# Powersupply.net
KiCad netlist of a schematic drawn in EAGLE
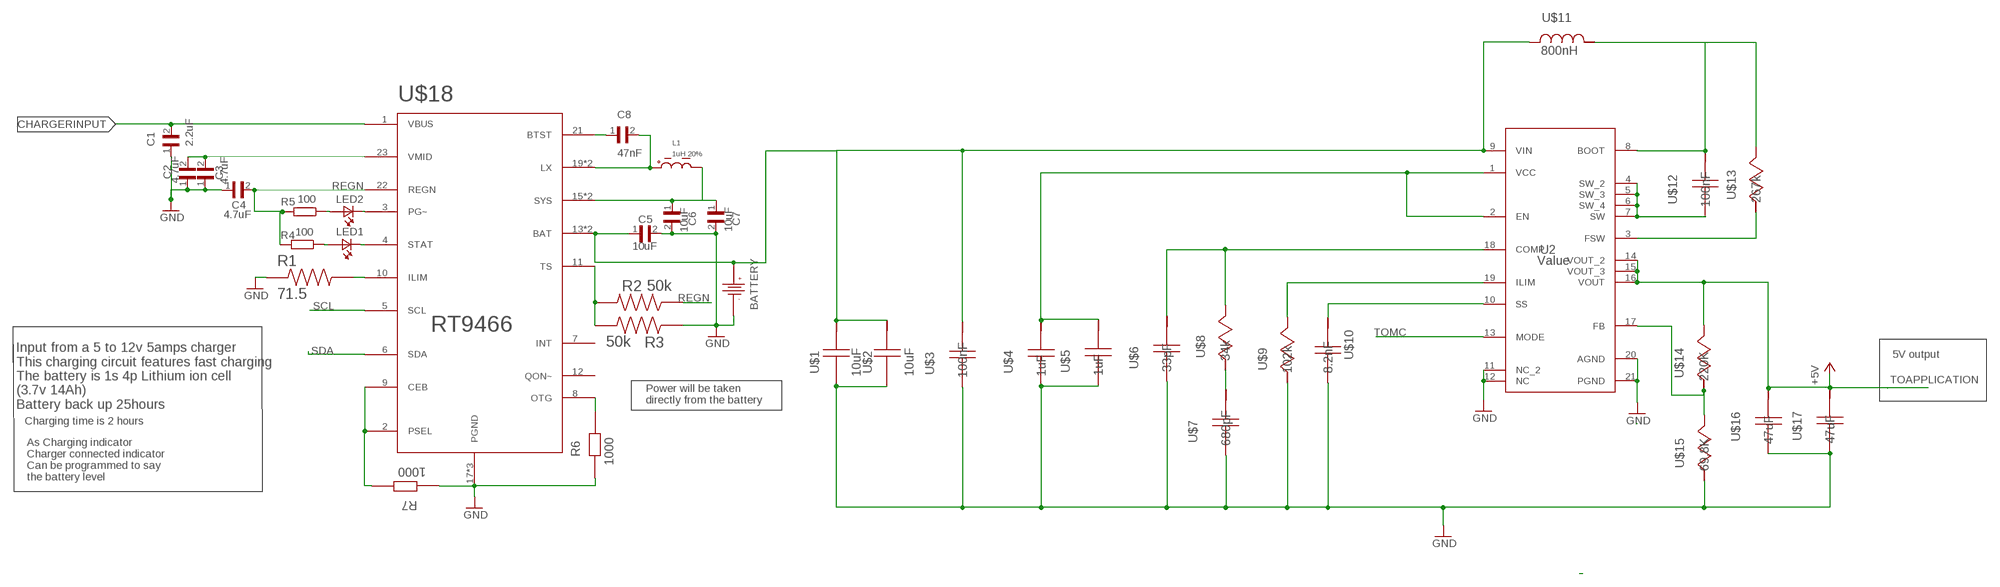
[diagram p0: schematic, sheet 1]

(export (version "E")
  (design (tool "Eeschema 10.0.6"))
  (components
    (comp (ref "BATT1")
      (value "BATPADS")
      (footprint "eagle-import:PADSBATT")
      (libsource (lib "eagle-import") (part "BATPADS"))
    )
    (comp (ref "C1")
      (value "2.2uF")
      (footprint "eagle-import:CAPC1005X70N")
      (fields
        (field (name "DIGI-KEY_PART_NUMBER") "490-12703-1-ND")
        (field (name "MF") "Murata")
        (field (name "MP") "GRM155R61E225KE11D")
      )
      (libsource (lib "eagle-import") (part "GRM155R61E225KE11D"))
    )
    (comp (ref "C2")
      (value "4.7uF")
      (footprint "eagle-import:CAPC1608X95N")
      (fields
        (field (name "DIGI-KEY_PART_NUMBER") "490-7203-1-ND")
        (field (name "MF") "Murata")
        (field (name "MP") "GRM188R61E475KE11D")
      )
      (libsource (lib "eagle-import") (part "GRM188R61E475KE11D"))
    )
    (comp (ref "C3")
      (value "4.7uF")
      (footprint "eagle-import:CAPC1608X95N")
      (fields
        (field (name "DIGI-KEY_PART_NUMBER") "490-7203-1-ND")
        (field (name "MF") "Murata")
        (field (name "MP") "GRM188R61E475KE11D")
      )
      (libsource (lib "eagle-import") (part "GRM188R61E475KE11D"))
    )
    (comp (ref "C4")
      (value "4.7uF")
      (footprint "eagle-import:CAPC1608X95N")
      (fields
        (field (name "DIGI-KEY_PART_NUMBER") "490-7203-1-ND")
        (field (name "MF") "Murata")
        (field (name "MP") "GRM188R61E475KE11D")
      )
      (libsource (lib "eagle-import") (part "GRM188R61E475KE11D"))
    )
    (comp (ref "C5")
      (value "10uF")
      (footprint "eagle-import:CAPC1608X50N")
      (fields
        (field (name "DIGI-KEY_PART_NUMBER") "490-16349-1-ND")
        (field (name "MF") "Murata")
        (field (name "MP") "GRM185R60J106ME15J")
      )
      (libsource (lib "eagle-import") (part "GRM185R60J106ME15J"))
    )
    (comp (ref "C6")
      (value "10uF")
      (footprint "eagle-import:CAPC1608X50N")
      (fields
        (field (name "DIGI-KEY_PART_NUMBER") "490-16349-1-ND")
        (field (name "MF") "Murata")
        (field (name "MP") "GRM185R60J106ME15J")
      )
      (libsource (lib "eagle-import") (part "GRM185R60J106ME15J"))
    )
    (comp (ref "C7")
      (value "10uF")
      (footprint "eagle-import:CAPC1608X50N")
      (fields
        (field (name "DIGI-KEY_PART_NUMBER") "490-16349-1-ND")
        (field (name "MF") "Murata")
        (field (name "MP") "GRM185R60J106ME15J")
      )
      (libsource (lib "eagle-import") (part "GRM185R60J106ME15J"))
    )
    (comp (ref "C8")
      (value "47nF")
      (footprint "eagle-import:CAPC0603X33N")
      (fields
        (field (name "DIGI-KEY_PART_NUMBER") "490-7227-1-ND")
        (field (name "MF") "Murata")
        (field (name "MP") "GRM033R61C473KE84D")
      )
      (libsource (lib "eagle-import") (part "GRM033R61C473KE84D"))
    )
    (comp (ref "L1")
      (value "1uH 20%")
      (footprint "eagle-import:4020")
      (fields (field (name "MANUFACTURER") "Würth Elektronik") (field (name "PARTNO") "74438356010"))
      (libsource (lib "eagle-import") (part "74438356010"))
    )
    (comp (ref "LED1")
      (value "LTST-C191KGKT")
      (footprint "eagle-import:0603")
      (fields (field (name "DIGI-KEY_PART_NUMBER") "160-1446-1-ND") (field (name "MF") "Lite-On Inc."))
      (libsource (lib "eagle-import") (part "LTST-C191KGKT"))
    )
    (comp (ref "LED2")
      (value "LTST-C191KGKT")
      (footprint "eagle-import:0603")
      (fields (field (name "DIGI-KEY_PART_NUMBER") "160-1446-1-ND") (field (name "MF") "Lite-On Inc."))
      (libsource (lib "eagle-import") (part "LTST-C191KGKT"))
    )
    (comp (ref "R1")
      (value "71.5")
      (footprint "eagle-import:RESC1005X40N")
      (fields
        (field (name "DIGI-KEY_PART_NUMBER") "YAG3223CT-ND")
        (field (name "MF") "Yageo")
        (field (name "MP") "RC0402FR-0771R5L")
      )
      (libsource (lib "eagle-import") (part "RC0402FR-0771R5L"))
    )
    (comp (ref "R2")
      (value "50k")
      (footprint "eagle-import:RESC1608X55N")
      (fields
        (field (name "DIGI-KEY_PART_NUMBER") "P49.9KDBCT-ND")
        (field (name "MF") "Panasonic")
        (field (name "MP") "ERA-3AEB4992V")
      )
      (libsource (lib "eagle-import") (part "ERA-3AEB4992V"))
    )
    (comp (ref "R3")
      (value "50k")
      (footprint "eagle-import:RESC1608X55N")
      (fields
        (field (name "DIGI-KEY_PART_NUMBER") "P49.9KDBCT-ND")
        (field (name "MF") "Panasonic")
        (field (name "MP") "ERA-3AEB4992V")
      )
      (libsource (lib "eagle-import") (part "ERA-3AEB4992V"))
    )
    (comp (ref "R4")
      (value "RX0402_100")
      (footprint "eagle-import:RC0402_100")
      (libsource (lib "eagle-import") (part "RX0402_100"))
    )
    (comp (ref "R5")
      (value "RX0402_100")
      (footprint "eagle-import:RC0402_100")
      (libsource (lib "eagle-import") (part "RX0402_100"))
    )
    (comp (ref "R6")
      (value "1000")
      (footprint "eagle-import:RESC1005X40N")
      (fields
        (field (name "DIGI-KEY_PART_NUMBER") "P1.0KJCT-ND")
        (field (name "MF") "Panasonic Electronic")
        (field (name "MP") "ERJ-2GEJ102X")
      )
      (libsource (lib "eagle-import") (part "ERJ-2GEJ102X"))
    )
    (comp (ref "R7")
      (value "1000")
      (footprint "eagle-import:RESC1005X40N")
      (fields
        (field (name "DIGI-KEY_PART_NUMBER") "P1.0KJCT-ND")
        (field (name "MF") "Panasonic Electronic")
        (field (name "MP") "ERJ-2GEJ102X")
      )
      (libsource (lib "eagle-import") (part "ERJ-2GEJ102X"))
    )
    (comp (ref "U$1")
      (value "10uF")
      (footprint "eagle-import:1206_190")
      (fields (field (name "MANUFACTURER_PART_NUMBER") "CC1206ZKY5V7BB106"))
      (libsource (lib "eagle-import") (part "CC1206ZKY5V7BB106"))
    )
    (comp (ref "U$2")
      (value "10uF")
      (footprint "eagle-import:1206_190")
      (fields (field (name "MANUFACTURER_PART_NUMBER") "CC1206ZKY5V7BB106"))
      (libsource (lib "eagle-import") (part "CC1206ZKY5V7BB106"))
    )
    (comp (ref "U$3")
      (value "100nF")
      (footprint "eagle-import:0402")
      (fields (field (name "MANUFACTURER_PART_NUMBER") "CC0402KRX7R6BB104"))
      (libsource (lib "eagle-import") (part "CC0402KRX7R6BB104"))
    )
    (comp (ref "U$4")
      (value "1uF")
      (footprint "eagle-import:0603")
      (fields (field (name "MANUFACTURER_PART_NUMBER") "EMK107B7105KAT") (field (name "SPICEPREFIX") "B"))
      (libsource (lib "eagle-import") (part "EMK107B7105KA-T"))
    )
    (comp (ref "U$5")
      (value "1uF")
      (footprint "eagle-import:0603")
      (fields (field (name "MANUFACTURER_PART_NUMBER") "EMK107B7105KAT"))
      (libsource (lib "eagle-import") (part "EMK107B7105KA-T"))
    )
    (comp (ref "U$6")
      (value "33pF")
      (footprint "eagle-import:0402")
      (fields (field (name "MANUFACTURER_PART_NUMBER") "885012005043"))
      (libsource (lib "eagle-import") (part "885012005043"))
    )
    (comp (ref "U$7")
      (value "680pF")
      (footprint "eagle-import:0603")
      (fields (field (name "MANUFACTURER_PART_NUMBER") "CL10C681JA8NNNC"))
      (libsource (lib "eagle-import") (part "CL10C681JA8NNNC"))
    )
    (comp (ref "U$8")
      (value "34k")
      (footprint "eagle-import:0402")
      (fields
        (field (name "MANUFACTURER_PART_NUMBER") "CRCW040234K0FKED")
        (field (name "POWER") "0.063")
        (field (name "TOLERANCE") "1.0")
      )
      (libsource (lib "eagle-import") (part "CRCW040234K0FKED"))
    )
    (comp (ref "U$9")
      (value "102k")
      (footprint "eagle-import:0402")
      (fields
        (field (name "MANUFACTURER_PART_NUMBER") "CRCW0402102KFKED")
        (field (name "POWER") "0.063")
        (field (name "TOLERANCE") "1.0")
      )
      (libsource (lib "eagle-import") (part "CRCW0402102KFKED"))
    )
    (comp (ref "U$10")
      (value "8.2nF")
      (footprint "eagle-import:0402")
      (fields (field (name "MANUFACTURER_PART_NUMBER") "CC0402KRX7R7BB822"))
      (libsource (lib "eagle-import") (part "CC0402KRX7R7BB822"))
    )
    (comp (ref "U$11")
      (value "800nH")
      (footprint "eagle-import:XAL5020")
      (fields
        (field (name "MANUFACTURER") "CoilCraft")
        (field (name "MANUFACTURER_PART_NUMBER") "XAL5020801MEB")
      )
      (libsource (lib "eagle-import") (part "XAL5020-801MEB"))
    )
    (comp (ref "U$12")
      (value "100nF")
      (footprint "eagle-import:0402")
      (fields (field (name "MANUFACTURER_PART_NUMBER") "/CC0402KRX5R7BB104"))
      (libsource (lib "eagle-import") (part "CC0402KRX5R7BB104"))
    )
    (comp (ref "U$13")
      (value "267k")
      (footprint "eagle-import:0402")
      (fields
        (field (name "MANUFACTURER_PART_NUMBER") "CRCW0402267KFKED")
        (field (name "POWER") "0.063")
        (field (name "TOLERANCE") "1.0")
      )
      (libsource (lib "eagle-import") (part "CRCW0402267KFKED"))
    )
    (comp (ref "U$14")
      (value "220K")
      (footprint "eagle-import:0603")
      (fields
        (field (name "MANUFACTURER_PART_NUMBER") "RC0603FR07220KL")
        (field (name "POWER") "0.1")
        (field (name "TOLERANCE") "1.0")
      )
      (libsource (lib "eagle-import") (part "RC0603FR-07220KL"))
    )
    (comp (ref "U$15")
      (value "69.8K")
      (footprint "eagle-import:0402")
      (fields
        (field (name "MANUFACTURER_PART_NUMBER") "CRCW040269K8FKED")
        (field (name "POWER") "0.063")
        (field (name "TOLERANCE") "1.0")
      )
      (libsource (lib "eagle-import") (part "CRCW040269K8FKED"))
    )
    (comp (ref "U$16")
      (value "47uF")
      (footprint "eagle-import:2220_250")
      (fields (field (name "MANUFACTURER_PART_NUMBER") "C5750X5R1C476M230KA"))
      (libsource (lib "eagle-import") (part "C5750X5R1C476M230KA"))
    )
    (comp (ref "U$17")
      (value "47uF")
      (footprint "eagle-import:2220_250")
      (fields (field (name "MANUFACTURER_PART_NUMBER") "C5750X5R1C476M230KA"))
      (libsource (lib "eagle-import") (part "C5750X5R1C476M230KA"))
    )
    (comp (ref "U$18")
      (value "RT9466")
      (footprint "eagle-import:V_W_U_XQFN4_4-24")
      (fields (field (name "MANUFACTURER") "Richtek USA Inc."))
      (libsource (lib "eagle-import") (part "RT9466"))
    )
    (comp (ref "U2")
      (value "Value")
      (footprint "eagle-import:RHL0020A")
      (fields
        (field (name "ALTERNATEPARTNUMBER") "TPS61088RHLT")
        (field (name "MANUFACTURER") "Texas Instruments")
        (field (name "MANUFACTURER_PART_NUMBER") "TPS61088RHLR")
      )
      (libsource (lib "eagle-import") (part "TPS61088RHLR"))
    )
  )
  (nets
    (net (code "1") (name "+5V") (class "Default")
      (node (ref "U$14") (pin "1") (pinfunction "1_1") (pintype "passive"))
      (node (ref "U$16") (pin "1") (pinfunction "1_1") (pintype "passive"))
      (node (ref "U$17") (pin "1") (pinfunction "1_1") (pintype "passive"))
      (node (ref "U2") (pin "14") (pinfunction "VOUT_2_14") (pintype "power_in"))
      (node (ref "U2") (pin "15") (pinfunction "VOUT_3_15") (pintype "power_in"))
      (node (ref "U2") (pin "16") (pinfunction "VOUT_16") (pintype "power_in"))
    )
    (net (code "2") (name "/REGN") (class "Default")
      (node (ref "C4") (pin "2") (pinfunction "2_2") (pintype "passive"))
      (node (ref "R2") (pin "1") (pinfunction "1_1") (pintype "passive"))
      (node (ref "R4") (pin "P$2") (pinfunction "2_P$2") (pintype "passive"))
      (node (ref "R5") (pin "P$2") (pinfunction "2_P$2") (pintype "passive"))
      (node (ref "U$18") (pin "22") (pinfunction "REGN_22") (pintype "bidirectional"))
    )
    (net (code "3") (name "/SCL") (class "Default")
      (node (ref "U$18") (pin "5") (pinfunction "SCL_5") (pintype "bidirectional"))
    )
    (net (code "4") (name "/SDA") (class "Default")
      (node (ref "U$18") (pin "6") (pinfunction "SDA_6") (pintype "bidirectional"))
    )
    (net (code "5") (name "/TOMC") (class "Default")
      (node (ref "U2") (pin "13") (pinfunction "MODE_13") (pintype "input"))
    )
    (net (code "6") (name "CHARGERINPUT") (class "Default")
      (node (ref "C1") (pin "2") (pinfunction "2_2") (pintype "passive"))
      (node (ref "U$18") (pin "1") (pinfunction "VBUS_1") (pintype "bidirectional"))
    )
    (net (code "7") (name "GND") (class "Default")
      (node (ref "BATT1") (pin "2") (pinfunction "P$2_2") (pintype "bidirectional"))
      (node (ref "C1") (pin "1") (pinfunction "1_1") (pintype "passive"))
      (node (ref "C2") (pin "1") (pinfunction "1_1") (pintype "passive"))
      (node (ref "C3") (pin "1") (pinfunction "1_1") (pintype "passive"))
      (node (ref "C4") (pin "1") (pinfunction "1_1") (pintype "passive"))
      (node (ref "C5") (pin "2") (pinfunction "2_2") (pintype "passive"))
      (node (ref "C6") (pin "2") (pinfunction "2_2") (pintype "passive"))
      (node (ref "C7") (pin "2") (pinfunction "2_2") (pintype "passive"))
      (node (ref "R1") (pin "1") (pinfunction "1_1") (pintype "passive"))
      (node (ref "R3") (pin "2") (pinfunction "2_2") (pintype "passive"))
      (node (ref "R6") (pin "1") (pinfunction "1_1") (pintype "bidirectional"))
      (node (ref "R7") (pin "1") (pinfunction "1_1") (pintype "bidirectional"))
      (node (ref "U$1") (pin "2") (pinfunction "2_2") (pintype "passive"))
      (node (ref "U$10") (pin "2") (pinfunction "2_2") (pintype "passive"))
      (node (ref "U$15") (pin "2") (pinfunction "2_2") (pintype "passive"))
      (node (ref "U$16") (pin "2") (pinfunction "2_2") (pintype "passive"))
      (node (ref "U$17") (pin "2") (pinfunction "2_2") (pintype "passive"))
      (node (ref "U$18") (pin "17") (pinfunction "PGND_17") (pintype "bidirectional"))
      (node (ref "U$18") (pin "18") (pinfunction "PGND_18") (pintype "bidirectional"))
      (node (ref "U$18") (pin "25") (pinfunction "PGND_25") (pintype "bidirectional"))
      (node (ref "U$2") (pin "2") (pinfunction "2_2") (pintype "passive"))
      (node (ref "U$3") (pin "2") (pinfunction "2_2") (pintype "passive"))
      (node (ref "U$4") (pin "2") (pinfunction "2_2") (pintype "passive"))
      (node (ref "U$5") (pin "2") (pinfunction "2_2") (pintype "passive"))
      (node (ref "U$6") (pin "2") (pinfunction "2_2") (pintype "passive"))
      (node (ref "U$7") (pin "2") (pinfunction "2_2") (pintype "passive"))
      (node (ref "U$9") (pin "2") (pinfunction "2_2") (pintype "passive"))
      (node (ref "U2") (pin "11") (pinfunction "NC_2_11") (pintype "passive"))
      (node (ref "U2") (pin "12") (pinfunction "NC_12") (pintype "passive"))
      (node (ref "U2") (pin "20") (pinfunction "AGND_20") (pintype "power_in"))
      (node (ref "U2") (pin "21") (pinfunction "PGND_21") (pintype "power_in"))
    )
    (net (code "8") (name "Net-(BATT1-P$1)") (class "Default")
      (node (ref "BATT1") (pin "1") (pinfunction "P$1_1") (pintype "bidirectional"))
      (node (ref "C5") (pin "1") (pinfunction "1_1") (pintype "passive"))
      (node (ref "U$1") (pin "1") (pinfunction "1_1") (pintype "passive"))
      (node (ref "U$11") (pin "1") (pinfunction "1_1") (pintype "passive"))
      (node (ref "U$18") (pin "13") (pinfunction "BAT_13") (pintype "bidirectional"))
      (node (ref "U$18") (pin "14") (pinfunction "BAT_14") (pintype "bidirectional"))
      (node (ref "U$2") (pin "1") (pinfunction "1_1") (pintype "passive"))
      (node (ref "U$3") (pin "1") (pinfunction "1_1") (pintype "passive"))
      (node (ref "U2") (pin "9") (pinfunction "VIN_9") (pintype "power_in"))
    )
    (net (code "9") (name "Net-(C6-Pad1)") (class "Default")
      (node (ref "C6") (pin "1") (pinfunction "1_1") (pintype "passive"))
      (node (ref "C7") (pin "1") (pinfunction "1_1") (pintype "passive"))
      (node (ref "L1") (pin "P$2") (pinfunction "P$2_P$2") (pintype "bidirectional"))
      (node (ref "U$18") (pin "15") (pinfunction "SYS_15") (pintype "bidirectional"))
      (node (ref "U$18") (pin "16") (pinfunction "SYS_16") (pintype "bidirectional"))
    )
    (net (code "10") (name "Net-(C8-Pad2)") (class "Default")
      (node (ref "C8") (pin "2") (pinfunction "2_2") (pintype "passive"))
      (node (ref "L1") (pin "P$1") (pinfunction "P$1_P$1") (pintype "bidirectional"))
      (node (ref "U$18") (pin "19") (pinfunction "LX_19") (pintype "bidirectional"))
      (node (ref "U$18") (pin "20") (pinfunction "LX_20") (pintype "bidirectional"))
    )
    (net (code "11") (name "Net-(LED1-A2)") (class "Default")
      (node (ref "LED1") (pin "2") (pinfunction "A2_2") (pintype "passive"))
      (node (ref "R4") (pin "P$1") (pinfunction "1_P$1") (pintype "passive"))
    )
    (net (code "12") (name "Net-(LED1-K2)") (class "Default")
      (node (ref "LED1") (pin "1") (pinfunction "K2_1") (pintype "passive"))
      (node (ref "U$18") (pin "4") (pinfunction "STAT_4") (pintype "bidirectional"))
    )
    (net (code "13") (name "Net-(LED2-A2)") (class "Default")
      (node (ref "LED2") (pin "2") (pinfunction "A2_2") (pintype "passive"))
      (node (ref "R5") (pin "P$1") (pinfunction "1_P$1") (pintype "passive"))
    )
    (net (code "14") (name "Net-(LED2-K2)") (class "Default")
      (node (ref "LED2") (pin "1") (pinfunction "K2_1") (pintype "passive"))
      (node (ref "U$18") (pin "3") (pinfunction "PG~{}_3") (pintype "bidirectional"))
    )
    (net (code "15") (name "Net-(U$7-Pad1)") (class "Default")
      (node (ref "U$7") (pin "1") (pinfunction "1_1") (pintype "passive"))
      (node (ref "U$8") (pin "2") (pinfunction "2_2") (pintype "passive"))
    )
    (net (code "16") (name "Net-(U$18-BTST)") (class "Default")
      (node (ref "C8") (pin "1") (pinfunction "1_1") (pintype "passive"))
      (node (ref "U$18") (pin "21") (pinfunction "BTST_21") (pintype "bidirectional"))
    )
    (net (code "17") (name "Net-(U$18-CEB)") (class "Default")
      (node (ref "R7") (pin "2") (pinfunction "2_2") (pintype "bidirectional"))
      (node (ref "U$18") (pin "2") (pinfunction "PSEL_2") (pintype "bidirectional"))
      (node (ref "U$18") (pin "9") (pinfunction "CEB_9") (pintype "bidirectional"))
    )
    (net (code "18") (name "Net-(U$18-ILIM)") (class "Default")
      (node (ref "R1") (pin "2") (pinfunction "2_2") (pintype "passive"))
      (node (ref "U$18") (pin "10") (pinfunction "ILIM_10") (pintype "bidirectional"))
    )
    (net (code "19") (name "Net-(U$18-OTG)") (class "Default")
      (node (ref "R6") (pin "2") (pinfunction "2_2") (pintype "bidirectional"))
      (node (ref "U$18") (pin "8") (pinfunction "OTG_8") (pintype "bidirectional"))
    )
    (net (code "20") (name "Net-(U$18-TS)") (class "Default")
      (node (ref "R2") (pin "2") (pinfunction "2_2") (pintype "passive"))
      (node (ref "R3") (pin "1") (pinfunction "1_1") (pintype "passive"))
      (node (ref "U$18") (pin "11") (pinfunction "TS_11") (pintype "bidirectional"))
    )
    (net (code "21") (name "Net-(U$18-VMID)") (class "Default")
      (node (ref "C2") (pin "2") (pinfunction "2_2") (pintype "passive"))
      (node (ref "C3") (pin "2") (pinfunction "2_2") (pintype "passive"))
      (node (ref "U$18") (pin "23") (pinfunction "VMID_23") (pintype "bidirectional"))
    )
    (net (code "22") (name "Net-(U2-BOOT)") (class "Default")
      (node (ref "U$11") (pin "2") (pinfunction "2_2") (pintype "passive"))
      (node (ref "U$12") (pin "1") (pinfunction "1_1") (pintype "passive"))
      (node (ref "U$13") (pin "1") (pinfunction "1_1") (pintype "passive"))
      (node (ref "U2") (pin "8") (pinfunction "BOOT_8") (pintype "power_in"))
    )
    (net (code "23") (name "Net-(U2-COMP)") (class "Default")
      (node (ref "U$6") (pin "1") (pinfunction "1_1") (pintype "passive"))
      (node (ref "U$8") (pin "1") (pinfunction "1_1") (pintype "passive"))
      (node (ref "U2") (pin "18") (pinfunction "COMP_18") (pintype "output"))
    )
    (net (code "24") (name "Net-(U2-EN)") (class "Default")
      (node (ref "U$4") (pin "1") (pinfunction "1_1") (pintype "passive"))
      (node (ref "U$5") (pin "1") (pinfunction "1_1") (pintype "passive"))
      (node (ref "U2") (pin "1") (pinfunction "VCC_1") (pintype "power_in"))
      (node (ref "U2") (pin "2") (pinfunction "EN_2") (pintype "input"))
    )
    (net (code "25") (name "Net-(U2-FB)") (class "Default")
      (node (ref "U$14") (pin "2") (pinfunction "2_2") (pintype "passive"))
      (node (ref "U$15") (pin "1") (pinfunction "1_1") (pintype "passive"))
      (node (ref "U2") (pin "17") (pinfunction "FB_17") (pintype "input"))
    )
    (net (code "26") (name "Net-(U2-FSW)") (class "Default")
      (node (ref "U$13") (pin "2") (pinfunction "2_2") (pintype "passive"))
      (node (ref "U2") (pin "3") (pinfunction "FSW_3") (pintype "input"))
    )
    (net (code "27") (name "Net-(U2-ILIM)") (class "Default")
      (node (ref "U$9") (pin "1") (pinfunction "1_1") (pintype "passive"))
      (node (ref "U2") (pin "19") (pinfunction "ILIM_19") (pintype "input"))
    )
    (net (code "28") (name "Net-(U2-SS)") (class "Default")
      (node (ref "U$10") (pin "1") (pinfunction "1_1") (pintype "passive"))
      (node (ref "U2") (pin "10") (pinfunction "SS_10") (pintype "input"))
    )
    (net (code "29") (name "Net-(U2-SW)") (class "Default")
      (node (ref "U$12") (pin "2") (pinfunction "2_2") (pintype "passive"))
      (node (ref "U2") (pin "4") (pinfunction "SW_2_4") (pintype "power_in"))
      (node (ref "U2") (pin "5") (pinfunction "SW_3_5") (pintype "power_in"))
      (node (ref "U2") (pin "6") (pinfunction "SW_4_6") (pintype "power_in"))
      (node (ref "U2") (pin "7") (pinfunction "SW_7") (pintype "power_in"))
    )
    (net (code "30") (name "unconnected-(U$18-INT-Pad7)") (class "Default")
      (node (ref "U$18") (pin "7") (pinfunction "INT_7") (pintype "bidirectional"))
    )
    (net (code "31") (name "unconnected-(U$18-QON~{}-Pad12)") (class "Default")
      (node (ref "U$18") (pin "12") (pinfunction "QON~{}_12") (pintype "bidirectional"))
    )
  )
)
